# Power_SarSol.net
KiCad netlist of a schematic drawn in Altium Designer
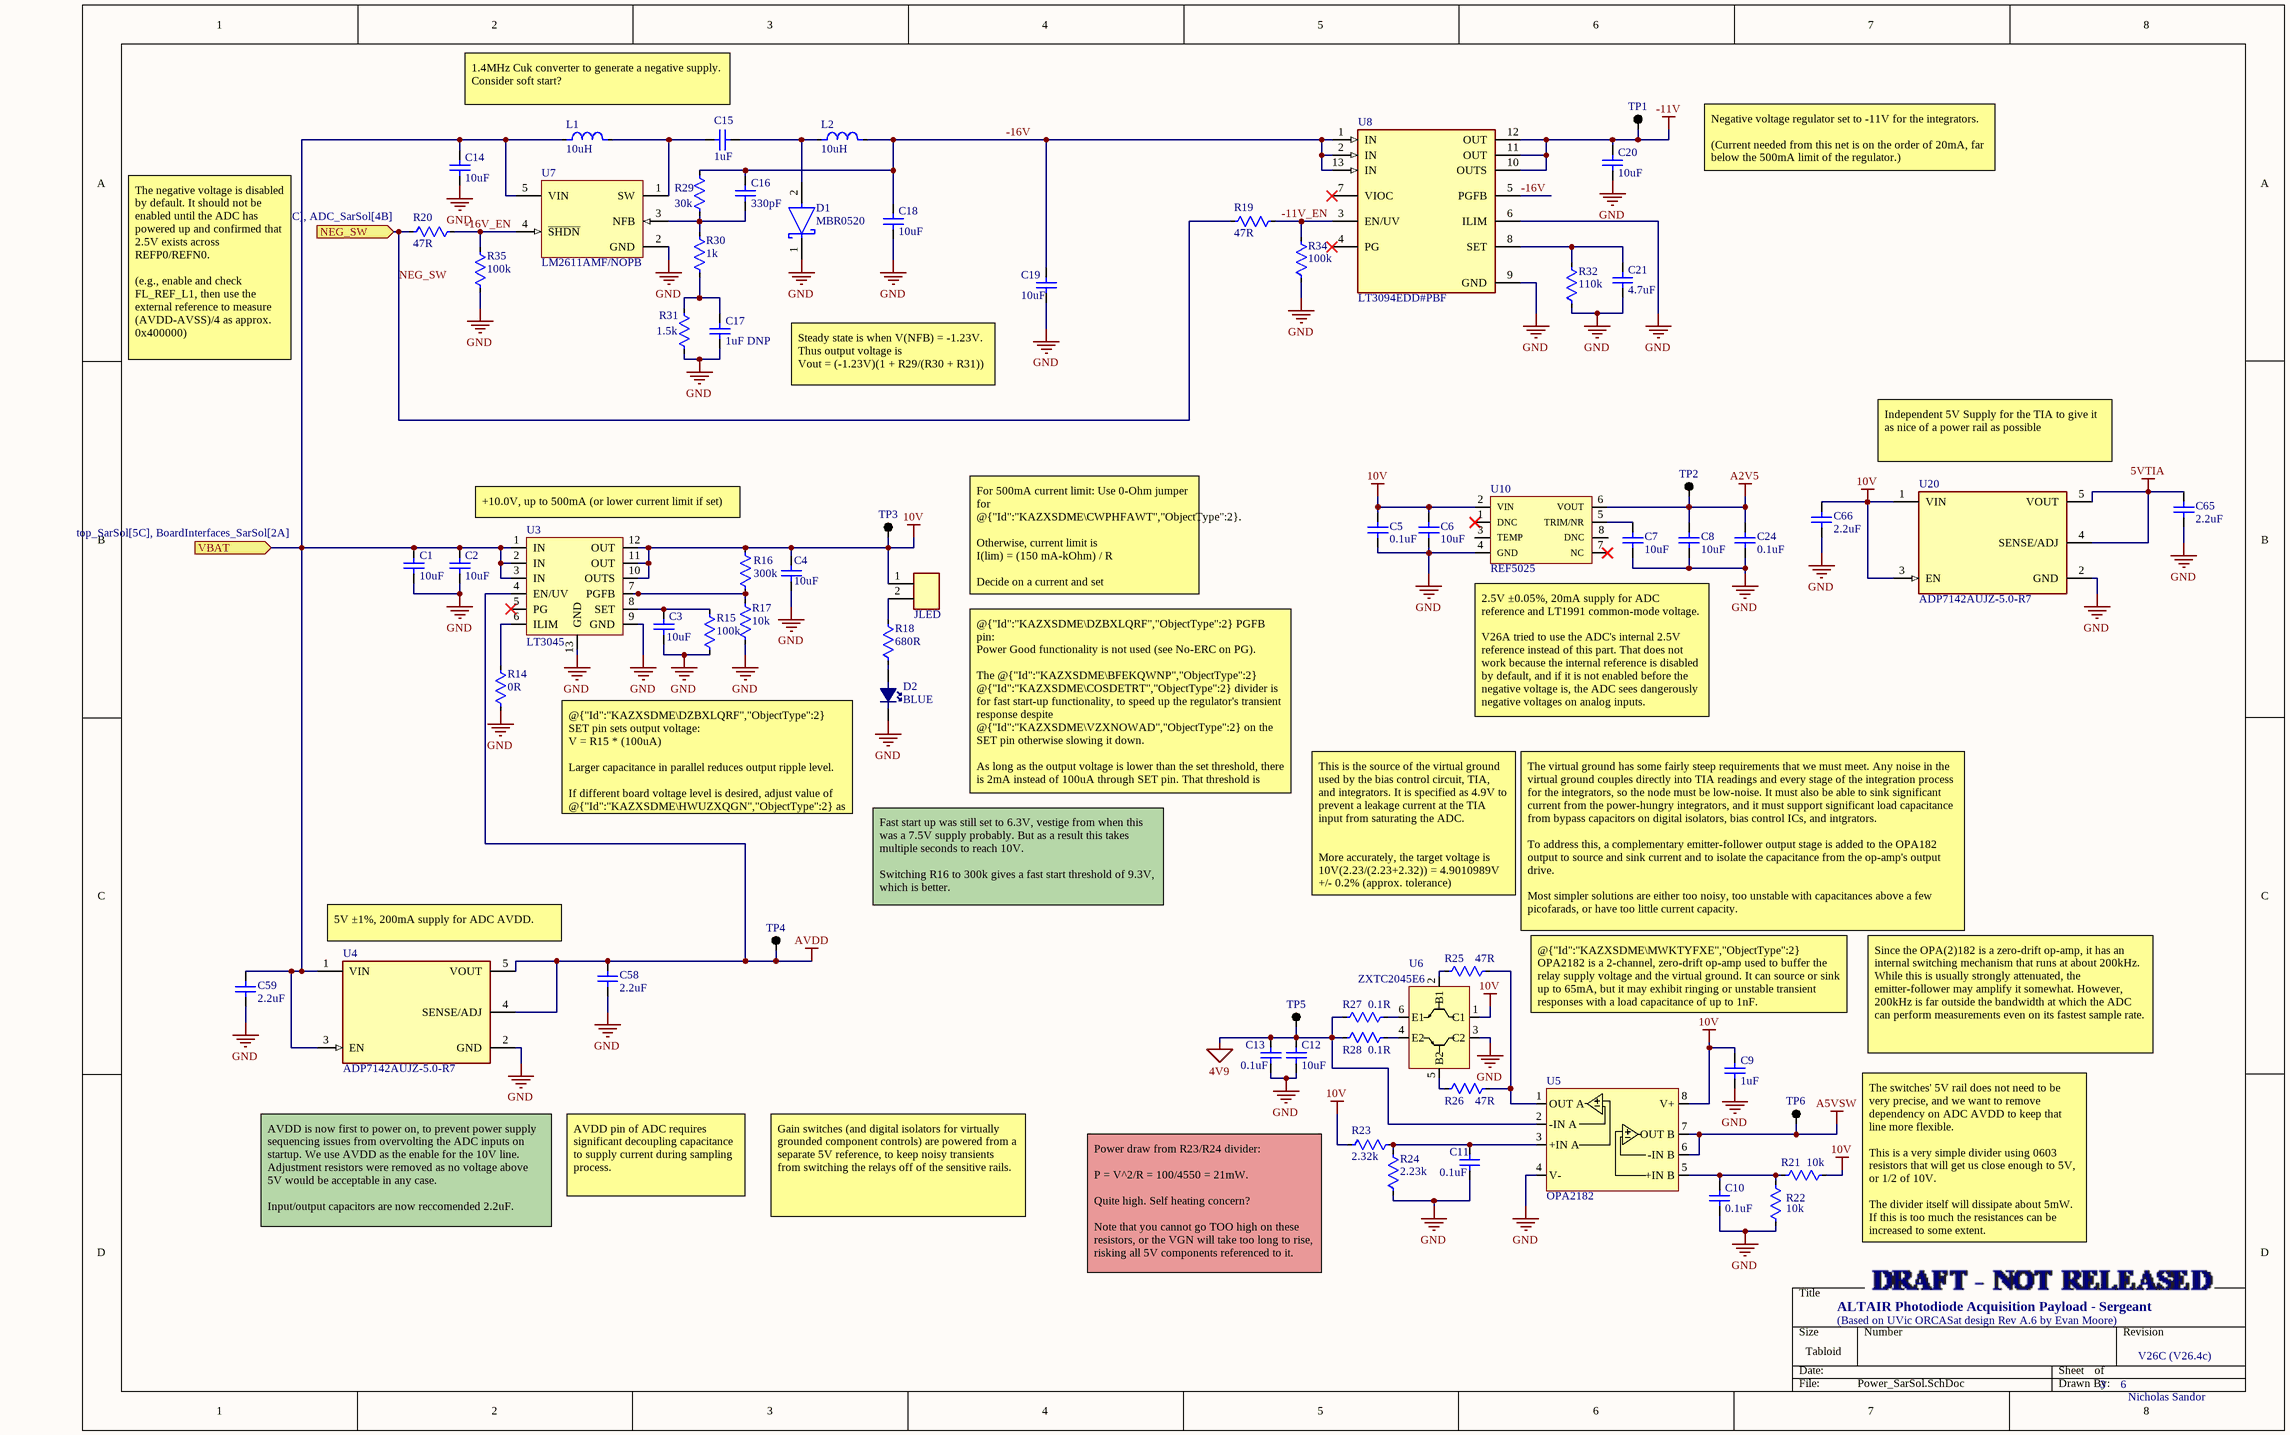
[diagram p0: Power_SarSol.SchDoc]

(export (version "E")
  (design (tool "Eeschema 10.0.6"))
  (components
    (comp (ref "C1")
      (value "10uF")
      (footprint "CAP 1206 IPC LOW DENSITY")
      (description "Murata GRT319R6YA106KE01D - Cap Ceramic 10uF 35V X5R 10% Pad SMD 1206 85C Automotive T/R")
      (fields (field (name "MF") "Murata") (field (name "MP") "GRT319R6YA106KE01D"))
      (libsource (lib "ALTAIR_PD_Capacitors") (part "CAP"))
    )
    (comp (ref "C2")
      (value "10uF")
      (footprint "CAP 1206 IPC LOW DENSITY")
      (description "Murata GRT319R6YA106KE01D - Cap Ceramic 10uF 35V X5R 10% Pad SMD 1206 85C Automotive T/R")
      (fields (field (name "MF") "Murata") (field (name "MP") "GRT319R6YA106KE01D"))
      (libsource (lib "ALTAIR_PD_Capacitors") (part "CAP"))
    )
    (comp (ref "C3")
      (value "10uF")
      (footprint "CAP 1206 IPC LOW DENSITY")
      (description "Murata GRT319R6YA106KE01D - Cap Ceramic 10uF 35V X5R 10% Pad SMD 1206 85C Automotive T/R")
      (fields (field (name "MF") "Murata") (field (name "MP") "GRT319R6YA106KE01D"))
      (libsource (lib "ALTAIR_PD_Capacitors") (part "CAP"))
    )
    (comp (ref "C4")
      (value "10uF")
      (footprint "CAP 1206 IPC LOW DENSITY")
      (description "Murata GRT319R6YA106KE01D - Cap Ceramic 10uF 35V X5R 10% Pad SMD 1206 85C Automotive T/R")
      (fields (field (name "MF") "Murata") (field (name "MP") "GRT319R6YA106KE01D"))
      (libsource (lib "ALTAIR_PD_Capacitors") (part "CAP"))
    )
    (comp (ref "C5")
      (value "0.1uF")
      (footprint "CAP 0603 IPC MID DENSITY")
      (description "Kemet C0603C104K5RACAUTO - Cap Ceramic 0.1uF 50V X7R 10% 0603 125C Paper T/R")
      (fields (field (name "MF") "Kemet") (field (name "MP") "C0603C104K5RACAUTO"))
      (libsource (lib "ALTAIR_PD_Capacitors") (part "CAP"))
    )
    (comp (ref "C6")
      (value "10uF")
      (footprint "CAP 0805 IPC MID DENSITY")
      (description "Murata GRM21BR61E106KA73L - Cap Ceramic 10uF 10% 25V X5R 0805")
      (fields (field (name "MF") "Murata") (field (name "MP") "GRM21BR61E106KA73L"))
      (libsource (lib "ALTAIR_PD_Capacitors") (part "CAP"))
    )
    (comp (ref "C7")
      (value "10uF")
      (footprint "CAP 0805 IPC MID DENSITY")
      (description "Murata GRM21BR61E106KA73L - Cap Ceramic 10uF 10% 25V X5R 0805")
      (fields (field (name "MF") "Murata") (field (name "MP") "GRM21BR61E106KA73L"))
      (libsource (lib "ALTAIR_PD_Capacitors") (part "CAP"))
    )
    (comp (ref "C8")
      (value "10uF")
      (footprint "CAP 0805 IPC MID DENSITY")
      (description "Murata GRM21BR61E106KA73L - Cap Ceramic 10uF 10% 25V X5R 0805")
      (fields (field (name "MF") "Murata") (field (name "MP") "GRM21BR61E106KA73L"))
      (libsource (lib "ALTAIR_PD_Capacitors") (part "CAP"))
    )
    (comp (ref "C9")
      (value "1uF")
      (footprint "CAP 0603 IPC MID DENSITY")
      (description "Murata GRT188R61H105KE13D - Cap MLCC AEC-Q200 X5R 1uF 50V 0603")
      (fields (field (name "MF") "Murata") (field (name "MP") "GRT188R61H105KE13D"))
      (libsource (lib "ALTAIR_PD_Capacitors") (part "CAP"))
    )
    (comp (ref "C10")
      (value "0.1uF")
      (footprint "CAP 0603 IPC MID DENSITY")
      (description "Kemet C0603C104K5RACAUTO - Cap Ceramic 0.1uF 50V X7R 10% 0603 125C Paper T/R")
      (fields (field (name "MF") "Kemet") (field (name "MP") "C0603C104K5RACAUTO"))
      (libsource (lib "ALTAIR_PD_Capacitors") (part "CAP"))
    )
    (comp (ref "C11")
      (value "0.1uF")
      (footprint "CAP 0603 IPC MID DENSITY")
      (description "Kemet C0603C104K5RACAUTO - Cap Ceramic 0.1uF 50V X7R 10% 0603 125C Paper T/R")
      (fields (field (name "MF") "Kemet") (field (name "MP") "C0603C104K5RACAUTO"))
      (libsource (lib "ALTAIR_PD_Capacitors") (part "CAP"))
    )
    (comp (ref "C12")
      (value "10uF")
      (footprint "CAP 1206 IPC LOW DENSITY")
      (description "Murata GRT319R6YA106KE01D - Cap Ceramic 10uF 35V X5R 10% Pad SMD 1206 85C Automotive T/R")
      (fields (field (name "MF") "Murata") (field (name "MP") "GRT319R6YA106KE01D"))
      (libsource (lib "ALTAIR_PD_Capacitors") (part "CAP"))
    )
    (comp (ref "C13")
      (value "0.1uF")
      (footprint "CAP 0603 IPC MID DENSITY")
      (description "Kemet C0603C104K5RACAUTO - Cap Ceramic 0.1uF 50V X7R 10% 0603 125C Paper T/R")
      (fields (field (name "MF") "Kemet") (field (name "MP") "C0603C104K5RACAUTO"))
      (libsource (lib "ALTAIR_PD_Capacitors") (part "CAP"))
    )
    (comp (ref "C14")
      (value "10uF")
      (footprint "CAP 0805 IPC MID DENSITY")
      (description "Murata GRM21BR61E106KA73L - Cap Ceramic 10uF 10% 25V X5R 0805")
      (fields (field (name "MF") "Murata") (field (name "MP") "GRM21BR61E106KA73L"))
      (libsource (lib "ALTAIR_PD_Capacitors") (part "CAP"))
    )
    (comp (ref "C15")
      (value "1uF")
      (footprint "CAP 0603 IPC MID DENSITY")
      (description "Murata GRT188R61H105KE13D - Cap MLCC AEC-Q200 X5R 1uF 50V 0603")
      (fields (field (name "MF") "Murata") (field (name "MP") "GRT188R61H105KE13D"))
      (libsource (lib "ALTAIR_PD_Capacitors") (part "CAP"))
    )
    (comp (ref "C16")
      (value "330pF")
      (footprint "CAP 1206 NON-IPC KEMET NP0")
      (description "Kemet C1206C331J5GACTU - Cap Ceramic 330pF 50V 5% NP0 1206")
      (fields (field (name "MF") "Kemet") (field (name "MP") "C1206C331J5GACTU"))
      (libsource (lib "ALTAIR_PD_Capacitors") (part "CAP"))
    )
    (comp (ref "C17")
      (value "1uF DNP")
      (footprint "CAP 0603 IPC MID DENSITY")
      (description "Murata GRT188R61H105KE13D - Cap MLCC AEC-Q200 X5R 1uF 50V 0603")
      (fields (field (name "MF") "Murata") (field (name "MP") "GRT188R61H105KE13D"))
      (libsource (lib "ALTAIR_PD_Capacitors") (part "CAP"))
    )
    (comp (ref "C18")
      (value "10uF")
      (footprint "CAP 0805 IPC MID DENSITY")
      (description "Murata GRM21BR61E106KA73L - Cap Ceramic 10uF 10% 25V X5R 0805")
      (fields (field (name "MF") "Murata") (field (name "MP") "GRM21BR61E106KA73L"))
      (libsource (lib "ALTAIR_PD_Capacitors") (part "CAP"))
    )
    (comp (ref "C19")
      (value "10uF")
      (footprint "CAP 0805 IPC MID DENSITY")
      (description "Murata GRM21BR61E106KA73L - Cap Ceramic 10uF 10% 25V X5R 0805")
      (fields (field (name "MF") "Murata") (field (name "MP") "GRM21BR61E106KA73L"))
      (libsource (lib "ALTAIR_PD_Capacitors") (part "CAP"))
    )
    (comp (ref "C20")
      (value "10uF")
      (footprint "CAP 0805 IPC MID DENSITY")
      (description "Murata GRM21BR61E106KA73L - Cap Ceramic 10uF 10% 25V X5R 0805")
      (fields (field (name "MF") "Murata") (field (name "MP") "GRM21BR61E106KA73L"))
      (libsource (lib "ALTAIR_PD_Capacitors") (part "CAP"))
    )
    (comp (ref "C21")
      (value "4.7uF")
      (footprint "CAP 0805 NON-IPC KEMET X5R")
      (description "Kemet C0805C475K8PACTU - Cap Ceramic 4.7uF 10V X5R 0805")
      (fields (field (name "MF") "Kemet") (field (name "MP") "C0805C475K8PACTU"))
      (libsource (lib "ALTAIR_PD_Capacitors") (part "CAP"))
    )
    (comp (ref "C24")
      (value "0.1uF")
      (footprint "CAP 0603 IPC MID DENSITY")
      (description "Kemet C0603C104K5RACAUTO - Cap Ceramic 0.1uF 50V X7R 10% 0603 125C Paper T/R")
      (fields (field (name "MF") "Kemet") (field (name "MP") "C0603C104K5RACAUTO"))
      (libsource (lib "ALTAIR_PD_Capacitors") (part "CAP"))
    )
    (comp (ref "C58")
      (value "2.2uF")
      (footprint "CAP 1206 UNKNOWN")
      (description "Cap, Nonpolar, Any, Must choose footprint manually")
      (libsource (lib "ALTAIR_PD_Capacitors") (part "CAP"))
    )
    (comp (ref "C59")
      (value "2.2uF")
      (footprint "CAP 1206 UNKNOWN")
      (description "Cap, Nonpolar, Any, Must choose footprint manually")
      (libsource (lib "ALTAIR_PD_Capacitors") (part "CAP"))
    )
    (comp (ref "C65")
      (value "2.2uF")
      (footprint "CAP 1206 UNKNOWN")
      (description "Cap, Nonpolar, Any, Must choose footprint manually")
      (libsource (lib "ALTAIR_PD_Capacitors") (part "CAP"))
    )
    (comp (ref "C66")
      (value "2.2uF")
      (footprint "CAP 1206 UNKNOWN")
      (description "Cap, Nonpolar, Any, Must choose footprint manually")
      (libsource (lib "ALTAIR_PD_Capacitors") (part "CAP"))
    )
    (comp (ref "D1")
      (value "MBR0520")
      (footprint "SOD-123 ONSEMI SMALL PADS")
      (description "DIODE SCHOTTKY 20V 500MA SOD123")
      (fields (field (name "MF") "onsemi") (field (name "MP") "MBR0520LT1G"))
      (libsource (lib "ALTAIR_PD_Diodes") (part "Schottky"))
    )
    (comp (ref "D2")
      (value "BLUE")
      (footprint "LED 0603 MID DENSITY")
      (description "LED BLUE CLEAR 0603 SMD")
      (fields (field (name "MF") "Wurth Electronics") (field (name "MP") "150060BS75000"))
      (libsource (lib "ALTAIR_PD_Diodes") (part "LED-blue"))
    )
    (comp (ref "JLED")
      (value "JLED")
      (footprint "ALTAIR_PD_Headers:JUMPER 2POS 1MM PITCH THT")
      (description "2x1 Header THT 1mm Pitch")
      (fields
        (field (name "MF") "GCT (GLOBAL CONNECTOR TECHNOLOGY)")
        (field (name "MP") "BC020-02-A-0200-0300-L-G")
      )
      (libsource (lib "ALTAIR_PD_Headers") (part "BC020-02-A-0200-0300-L-G"))
    )
    (comp (ref "L1")
      (value "10uH")
      (footprint "IND VLS3012CX-1 NONSTANDARD TDK")
      (description "TDK VLS3012CX-100M-1 - Inductor 10uH 20% 1.25A 0.324Ohm NonstandardPkg")
      (fields (field (name "TOLERANCE") "20%") (field (name "MF") "TDK Corporation"))
      (libsource (lib "ALTAIR_PD_Inductors") (part "IND"))
    )
    (comp (ref "L2")
      (value "10uH")
      (footprint "IND VLS3012CX-1 NONSTANDARD TDK")
      (description "TDK VLS3012CX-100M-1 - Inductor 10uH 20% 1.25A 0.324Ohm NonstandardPkg")
      (fields (field (name "TOLERANCE") "20%") (field (name "MF") "TDK Corporation"))
      (libsource (lib "ALTAIR_PD_Inductors") (part "IND"))
    )
    (comp (ref "R14")
      (value "0R")
      (footprint "RES 0603 IPC MID DENSITY")
      (description "Vishay CRCW06030000Z0EA - Res 0 Ohms 1/8W SMD 0603")
      (fields (field (name "MF") "Vishay Dale") (field (name "MP") "CRCW06030000Z0EA"))
      (libsource (lib "ALTAIR_PD_Resistors") (part "RES"))
    )
    (comp (ref "R15")
      (value "100k")
      (footprint "RES 0603 IPC MID DENSITY")
      (description "Panasonic ERA-3ARB104V - Res SMD 0603 0.1% 0.10W T.C. 10ppm 100K")
      (fields (field (name "MF") "Panasonic Electronic Components") (field (name "MP") "ERA-3ARB104V"))
      (libsource (lib "ALTAIR_PD_Resistors") (part "RES"))
    )
    (comp (ref "R16")
      (value "300k")
      (footprint "RES 0603 IPC MID DENSITY")
      (description "Vishay MCT06030C2003FP500 - Res SMD 200kOhm 1% 1/10W 0603")
      (fields (field (name "MF") "Vishay Dale") (field (name "MP") "MCT06030C2003FP500"))
      (libsource (lib "ALTAIR_PD_Resistors") (part "RES"))
    )
    (comp (ref "R17")
      (value "10k")
      (footprint "RES 0603 IPC MID DENSITY")
      (description "Vishay CRCW060310K0FKEA SMD 0603 10k, CRCW e3 Series, 75V, thick film, 100mW")
      (fields (field (name "MF") "Vishay Dale") (field (name "MP") "CRCW060310K0FKEA"))
      (libsource (lib "ALTAIR_PD_Resistors") (part "RES"))
    )
    (comp (ref "R18")
      (value "680R")
      (footprint "RES 0603 IPC MID DENSITY")
      (description "Panasonic ERJ-3EKF6800V - Res SMD 680 Ohm 1% 1/10W 0603")
      (fields (field (name "MF") "Panasonic Electronic Components") (field (name "MP") "ERJ-3EKF6800V"))
      (libsource (lib "ALTAIR_PD_Resistors") (part "RES"))
    )
    (comp (ref "R19")
      (value "47R")
      (footprint "RES 0603 IPC MID DENSITY")
      (description "Vishay CRCW060347R0JNEA - Res 47Ohm 5% 1/8W SMD 0603")
      (fields (field (name "MF") "Vishay Dale") (field (name "MP") "CRCW060347R0JNEA"))
      (libsource (lib "ALTAIR_PD_Resistors") (part "RES"))
    )
    (comp (ref "R20")
      (value "47R")
      (footprint "RES 0603 IPC MID DENSITY")
      (description "Vishay CRCW060347R0JNEA - Res 47Ohm 5% 1/8W SMD 0603")
      (fields (field (name "MF") "Vishay Dale") (field (name "MP") "CRCW060347R0JNEA"))
      (libsource (lib "ALTAIR_PD_Resistors") (part "RES"))
    )
    (comp (ref "R21")
      (value "10k")
      (footprint "RES 0603 IPC MID DENSITY")
      (description "Vishay CRCW060310K0FKEA SMD 0603 10k, CRCW e3 Series, 75V, thick film, 100mW")
      (fields (field (name "MF") "Vishay Dale") (field (name "MP") "CRCW060310K0FKEA"))
      (libsource (lib "ALTAIR_PD_Resistors") (part "RES"))
    )
    (comp (ref "R22")
      (value "10k")
      (footprint "RES 0603 IPC MID DENSITY")
      (description "Vishay CRCW060310K0FKEA SMD 0603 10k, CRCW e3 Series, 75V, thick film, 100mW")
      (fields (field (name "MF") "Vishay Dale") (field (name "MP") "CRCW060310K0FKEA"))
      (libsource (lib "ALTAIR_PD_Resistors") (part "RES"))
    )
    (comp (ref "R23")
      (value "2.32k")
      (footprint "RES 0603 IPC MID DENSITY")
      (description "Vishay TNPW06032K32BEEA - Res 2.32k 0.1% 0.21W SMD 0603")
      (fields (field (name "MF") "Vishay Dale") (field (name "MP") "TNPW06032K32BEEA"))
      (libsource (lib "ALTAIR_PD_Resistors") (part "RES"))
    )
    (comp (ref "R24")
      (value "2.23k")
      (footprint "RES 0603 IPC MID DENSITY")
      (description "KOA Speer RN73R1JTTD2231B25 - Res 2.23k 0.1% 1/10W SMD 0603")
      (fields (field (name "MF") "KOA Speer Electronics, Inc.") (field (name "MP") "RN73R1JTTD2231B25"))
      (libsource (lib "ALTAIR_PD_Resistors") (part "RES"))
    )
    (comp (ref "R25")
      (value "47R")
      (footprint "RES 0402 NON-IPC SEI")
      (description "Stackpole RMCF0402JT47R0 - Res 47Ohm 5% 0.063W 0402 Thick Film AEC-Q200 compliant")
      (fields (field (name "MF") "Stackpole Electronics Inc.") (field (name "MP") "RMCF0402JT47R0"))
      (libsource (lib "ALTAIR_PD_Resistors") (part "RES"))
    )
    (comp (ref "R26")
      (value "47R")
      (footprint "RES 0402 NON-IPC SEI")
      (description "Stackpole RMCF0402JT47R0 - Res 47Ohm 5% 0.063W 0402 Thick Film AEC-Q200 compliant")
      (fields (field (name "MF") "Stackpole Electronics Inc.") (field (name "MP") "RMCF0402JT47R0"))
      (libsource (lib "ALTAIR_PD_Resistors") (part "RES"))
    )
    (comp (ref "R27")
      (value "0.1R")
      (footprint "RES 0402 NON-IPC YAGEO")
      (description "Yageo RL0402JR-070R1L - Res 0.1Ohm 5% 1/16W SMD 0402")
      (fields (field (name "MF") "YAGEO") (field (name "MP") "RL0402JR-070R1L"))
      (libsource (lib "ALTAIR_PD_Resistors") (part "RES"))
    )
    (comp (ref "R28")
      (value "0.1R")
      (footprint "RES 0402 NON-IPC YAGEO")
      (description "Yageo RL0402JR-070R1L - Res 0.1Ohm 5% 1/16W SMD 0402")
      (fields (field (name "MF") "YAGEO") (field (name "MP") "RL0402JR-070R1L"))
      (libsource (lib "ALTAIR_PD_Resistors") (part "RES"))
    )
    (comp (ref "R29")
      (value "30k")
      (footprint "RES 0805 IPC HIGH DENSITY")
      (description "Panasonic ERA-6AEB303V - Res 30kOhm 0.1% 1/8W 0805")
      (fields (field (name "MF") "Panasonic Electronic Components") (field (name "MP") "ERA-6AEB303V"))
      (libsource (lib "ALTAIR_PD_Resistors") (part "RES"))
    )
    (comp (ref "R30")
      (value "1k")
      (footprint "RES 0402 IPC LOW DENSITY YAGEO")
      (description "Yageo RC0402FR-071KL - Res 1kOhm 1% 1/16W 0402")
      (fields (field (name "MF") "YAGEO") (field (name "MP") "RC0402FR-071KL"))
      (libsource (lib "ALTAIR_PD_Resistors") (part "RES"))
    )
    (comp (ref "R31")
      (value "1.5k")
      (footprint "RES 1206 NON-IPC VISHAY")
      (description "Vishay TNPU12061K50BZEN00 - Res 1.5kOhm 0.1% 1/4W 1206")
      (fields (field (name "MF") "Vishay Dale") (field (name "MP") "TNPU12061K50BZEN00"))
      (libsource (lib "ALTAIR_PD_Resistors") (part "RES"))
    )
    (comp (ref "R32")
      (value "110k")
      (footprint "RES 0603 IPC MID DENSITY")
      (description "Panasonic ERA-3AEB114V - Res 110k 0.1% 1/10W SMD 0603")
      (fields (field (name "MF") "Panasonic Electronic Components") (field (name "MP") "ERA-3AEB114V"))
      (libsource (lib "ALTAIR_PD_Resistors") (part "RES"))
    )
    (comp (ref "R34")
      (value "100k")
      (footprint "RES 0603 IPC MID DENSITY")
      (description "Panasonic ERJ-3GEYJ104V - Res 100k 5% 1/10W SMD 0603")
      (fields (field (name "MF") "Panasonic Electronic Components") (field (name "MP") "ERJ-3GEYJ104V"))
      (libsource (lib "ALTAIR_PD_Resistors") (part "RES"))
    )
    (comp (ref "R35")
      (value "100k")
      (footprint "RES 0603 IPC MID DENSITY")
      (description "Panasonic ERJ-3GEYJ104V - Res 100k 5% 1/10W SMD 0603")
      (fields (field (name "MF") "Panasonic Electronic Components") (field (name "MP") "ERJ-3GEYJ104V"))
      (libsource (lib "ALTAIR_PD_Resistors") (part "RES"))
    )
    (comp (ref "TP1")
      (value "Testpoint")
      (footprint "TESTPOINT THT")
      (libsource (lib "ALTAIR_PD_Testpoint") (part "Testpoint"))
    )
    (comp (ref "TP2")
      (value "Testpoint")
      (footprint "TESTPOINT THT")
      (libsource (lib "ALTAIR_PD_Testpoint") (part "Testpoint"))
    )
    (comp (ref "TP3")
      (value "Testpoint")
      (footprint "TESTPOINT THT")
      (libsource (lib "ALTAIR_PD_Testpoint") (part "Testpoint"))
    )
    (comp (ref "TP4")
      (value "Testpoint")
      (footprint "TESTPOINT THT")
      (libsource (lib "ALTAIR_PD_Testpoint") (part "Testpoint"))
    )
    (comp (ref "TP5")
      (value "Testpoint")
      (footprint "TESTPOINT THT")
      (libsource (lib "ALTAIR_PD_Testpoint") (part "Testpoint"))
    )
    (comp (ref "TP6")
      (value "Testpoint")
      (footprint "TESTPOINT THT")
      (libsource (lib "ALTAIR_PD_Testpoint") (part "Testpoint"))
    )
    (comp (ref "U3")
      (value "LT3045")
      (footprint "12-TSOP 0.65MM PITCH 3MM WIDTH EP IPC MID DENSITY")
      (description "20V 500mA Ultralow Noise Ultrahigh PSRR Adjustable Linear Regulator 260V Dropout MSOP-12")
      (fields (field (name "MF") "Analog Devices / Linear Technology") (field (name "MP") "LT3045EMSE#PBF"))
      (libsource (lib "ALTAIR_PD_Regulators") (part "LT3045"))
    )
    (comp (ref "U4")
      (value "ADP7142AUJZ-5.0-R7")
      (footprint "SOT23-5 HIGH DENSITY AD")
      (description "1.2-40V 200mA Low Noise CMOS LDO Adjustable Linear Regulator TSOT23")
      (fields
        (field (name "OCTOPART") "https://octopart.com/adp7142aujz-r7-analog+devices-38928114")
        (field (name "MF") "Analog Devices")
      )
      (libsource (lib "ALTAIR_PD_Regulators") (part "ADP7142AUJZ-R7"))
    )
    (comp (ref "U5")
      (value "OPA2182")
      (footprint "8-TSSOP 0.65MM PITCH 4.4MM WIDTH IPC MID DENSITY")
      (fields (field (name "MF") "Texas Instruments") (field (name "MP") "OPA2182IDGKR"))
      (libsource (lib "ALTAIR_PD_Amplifiers") (part "OPA2182IDBV"))
    )
    (comp (ref "U6")
      (value "ZXTC2045E6")
      (footprint "SOT23-6 NON-IPC DIODES")
      (description "BJT Array, 1NPN 1PNP, VCE(sat) 375mV, hFE 300, Breakdown 30V, 6-SOT-23")
      (fields (field (name "MF") "Diodes Incorporated") (field (name "MP") "ZXTC2045E6TA"))
      (libsource (lib "ALTAIR_PD_BJTs") (part "ZXTC2045E6"))
    )
    (comp (ref "U7")
      (value "LM2611AMF/NOPB")
      (footprint "SOT23-5 MID DENSITY")
      (description "1.4MHz Cuk Converter, 5-pin SOT-23, Pb-Free")
      (fields (field (name "MF") "Texas Instruments"))
      (libsource (lib "ALTAIR_PD_Converters") (part "LM2611AMF"))
    )
    (comp (ref "U8")
      (value "LT3094EDD#PBF")
      (footprint "12DFN 3x3MM EP IPC MID DENSITY")
      (description "-20V 500mA Ultralow Noise Ultrahigh PSRR Adjustable Negative Linear Regulator 12DFN")
      (fields (field (name "MF") "Analog Devices"))
      (libsource (lib "ALTAIR_PD_Regulators") (part "LT3094EDD#PBF"))
    )
    (comp (ref "U10")
      (value "REF5025")
      (footprint "8-TSOP 0.65MM PITCH 3MM WIDTH IPC MID DENSITY")
      (description "2.5V±0.05% Voltage Reference 8VSSOP")
      (fields (field (name "MF") "Texas Instruments") (field (name "MP") "REF5025IDGKR"))
      (libsource (lib "ALTAIR_PD_MiscPower") (part "REF5050IDGKR"))
    )
    (comp (ref "U20")
      (value "ADP7142AUJZ-5.0-R7")
      (footprint "SOT23-5 HIGH DENSITY AD")
      (description "1.2-40V 200mA Low Noise CMOS LDO Adjustable Linear Regulator TSOT23")
      (fields
        (field (name "OCTOPART") "https://octopart.com/adp7142aujz-r7-analog+devices-38928114")
        (field (name "MF") "Analog Devices")
      )
      (libsource (lib "ALTAIR_PD_Regulators") (part "ADP7142AUJZ-R7"))
    )
  )
  (nets
    (net (code "1") (name "-11V") (class "Default")
      (node (ref "C20") (pin "1") (pinfunction "1_1") (pintype "passive"))
      (node (ref "TP1") (pin "1") (pinfunction "1_1") (pintype "passive"))
      (node (ref "U8") (pin "10") (pinfunction "OUTS_10") (pintype "power_in"))
      (node (ref "U8") (pin "11") (pinfunction "OUT_11") (pintype "power_in"))
      (node (ref "U8") (pin "12") (pinfunction "OUT_12") (pintype "power_in"))
    )
    (net (code "2") (name "/-11V_EN") (class "Default")
      (node (ref "R19") (pin "1") (pinfunction "1_1") (pintype "passive"))
      (node (ref "R34") (pin "1") (pinfunction "1_1") (pintype "passive"))
      (node (ref "U8") (pin "3") (pinfunction "EN/UV_3") (pintype "passive"))
    )
    (net (code "3") (name "/-16V") (class "Default")
      (node (ref "C16") (pin "1") (pinfunction "1_1") (pintype "passive"))
      (node (ref "C18") (pin "1") (pinfunction "1_1") (pintype "passive"))
      (node (ref "C19") (pin "1") (pinfunction "1_1") (pintype "passive"))
      (node (ref "L2") (pin "2") (pinfunction "2_2") (pintype "passive"))
      (node (ref "R29") (pin "2") (pinfunction "2_2") (pintype "passive"))
      (node (ref "U8") (pin "1") (pinfunction "IN_1") (pintype "input"))
      (node (ref "U8") (pin "13") (pinfunction "IN_13") (pintype "input"))
      (node (ref "U8") (pin "2") (pinfunction "IN_2") (pintype "input"))
      (node (ref "U8") (pin "5") (pinfunction "PGFB_5") (pintype "passive"))
    )
    (net (code "4") (name "/-16V_EN") (class "Default")
      (node (ref "R20") (pin "1") (pinfunction "1_1") (pintype "passive"))
      (node (ref "R35") (pin "1") (pinfunction "1_1") (pintype "passive"))
      (node (ref "U7") (pin "4") (pinfunction "~{SHDN}_4") (pintype "input"))
    )
    (net (code "5") (name "/NEG_SW") (class "Default")
      (node (ref "R19") (pin "2") (pinfunction "2_2") (pintype "passive"))
      (node (ref "R20") (pin "2") (pinfunction "2_2") (pintype "passive"))
    )
    (net (code "6") (name "/VBAT") (class "Default")
      (node (ref "C1") (pin "2") (pinfunction "2_2") (pintype "passive"))
      (node (ref "C14") (pin "2") (pinfunction "2_2") (pintype "passive"))
      (node (ref "C2") (pin "2") (pinfunction "2_2") (pintype "passive"))
      (node (ref "C59") (pin "1") (pinfunction "1_1") (pintype "passive"))
      (node (ref "L1") (pin "1") (pinfunction "1_1") (pintype "passive"))
      (node (ref "U3") (pin "1") (pinfunction "IN_1") (pintype "passive"))
      (node (ref "U3") (pin "2") (pinfunction "IN_2") (pintype "passive"))
      (node (ref "U3") (pin "3") (pinfunction "IN_3") (pintype "passive"))
      (node (ref "U4") (pin "1") (pinfunction "VIN_1") (pintype "power_in"))
      (node (ref "U4") (pin "3") (pinfunction "EN_3") (pintype "input"))
      (node (ref "U7") (pin "5") (pinfunction "VIN_5") (pintype "power_in"))
    )
    (net (code "7") (name "4V9") (class "Default")
      (node (ref "C12") (pin "2") (pinfunction "2_2") (pintype "passive"))
      (node (ref "C13") (pin "2") (pinfunction "2_2") (pintype "passive"))
      (node (ref "R27") (pin "1") (pinfunction "1_1") (pintype "passive"))
      (node (ref "R28") (pin "1") (pinfunction "1_1") (pintype "passive"))
      (node (ref "TP5") (pin "1") (pinfunction "1_1") (pintype "passive"))
      (node (ref "U5") (pin "2") (pinfunction "-IN_A_2") (pintype "passive"))
    )
    (net (code "8") (name "5VTIA") (class "Default")
      (node (ref "C65") (pin "1") (pinfunction "1_1") (pintype "passive"))
      (node (ref "U20") (pin "4") (pinfunction "SENSE/ADJ_4") (pintype "passive"))
      (node (ref "U20") (pin "5") (pinfunction "VOUT_5") (pintype "passive"))
    )
    (net (code "9") (name "10V") (class "Default")
      (node (ref "C4") (pin "2") (pinfunction "2_2") (pintype "passive"))
      (node (ref "C5") (pin "1") (pinfunction "1_1") (pintype "passive"))
      (node (ref "C6") (pin "2") (pinfunction "2_2") (pintype "passive"))
      (node (ref "C66") (pin "1") (pinfunction "1_1") (pintype "passive"))
      (node (ref "C9") (pin "2") (pinfunction "2_2") (pintype "passive"))
      (node (ref "JLED") (pin "1") (pinfunction "1_1") (pintype "passive"))
      (node (ref "R16") (pin "2") (pinfunction "2_2") (pintype "passive"))
      (node (ref "R21") (pin "2") (pinfunction "2_2") (pintype "passive"))
      (node (ref "R23") (pin "2") (pinfunction "2_2") (pintype "passive"))
      (node (ref "TP3") (pin "1") (pinfunction "1_1") (pintype "passive"))
      (node (ref "U10") (pin "2") (pinfunction "VIN_2") (pintype "passive"))
      (node (ref "U20") (pin "1") (pinfunction "VIN_1") (pintype "power_in"))
      (node (ref "U20") (pin "3") (pinfunction "EN_3") (pintype "input"))
      (node (ref "U3") (pin "10") (pinfunction "OUTS_10") (pintype "passive"))
      (node (ref "U3") (pin "11") (pinfunction "OUT_11") (pintype "passive"))
      (node (ref "U3") (pin "12") (pinfunction "OUT_12") (pintype "passive"))
      (node (ref "U5") (pin "8") (pinfunction "V+_8") (pintype "passive"))
      (node (ref "U6") (pin "1") (pinfunction "C1_1") (pintype "passive"))
    )
    (net (code "10") (name "A2V5") (class "Default")
      (node (ref "C24") (pin "1") (pinfunction "1_1") (pintype "passive"))
      (node (ref "C8") (pin "2") (pinfunction "2_2") (pintype "passive"))
      (node (ref "TP2") (pin "1") (pinfunction "1_1") (pintype "passive"))
      (node (ref "U10") (pin "6") (pinfunction "VOUT_6") (pintype "passive"))
    )
    (net (code "11") (name "A5VSW") (class "Default")
      (node (ref "TP6") (pin "1") (pinfunction "1_1") (pintype "passive"))
      (node (ref "U5") (pin "6") (pinfunction "-IN_B_6") (pintype "passive"))
      (node (ref "U5") (pin "7") (pinfunction "OUT_B_7") (pintype "passive"))
    )
    (net (code "12") (name "AVDD") (class "Default")
      (node (ref "C58") (pin "1") (pinfunction "1_1") (pintype "passive"))
      (node (ref "TP4") (pin "1") (pinfunction "1_1") (pintype "passive"))
      (node (ref "U3") (pin "4") (pinfunction "EN/UV_4") (pintype "passive"))
      (node (ref "U4") (pin "4") (pinfunction "SENSE/ADJ_4") (pintype "passive"))
      (node (ref "U4") (pin "5") (pinfunction "VOUT_5") (pintype "passive"))
    )
    (net (code "13") (name "GND") (class "Default")
      (node (ref "C1") (pin "1") (pinfunction "1_1") (pintype "passive"))
      (node (ref "C10") (pin "1") (pinfunction "1_1") (pintype "passive"))
      (node (ref "C11") (pin "1") (pinfunction "1_1") (pintype "passive"))
      (node (ref "C12") (pin "1") (pinfunction "1_1") (pintype "passive"))
      (node (ref "C13") (pin "1") (pinfunction "1_1") (pintype "passive"))
      (node (ref "C14") (pin "1") (pinfunction "1_1") (pintype "passive"))
      (node (ref "C17") (pin "2") (pinfunction "2_2") (pintype "passive"))
      (node (ref "C18") (pin "2") (pinfunction "2_2") (pintype "passive"))
      (node (ref "C19") (pin "2") (pinfunction "2_2") (pintype "passive"))
      (node (ref "C2") (pin "1") (pinfunction "1_1") (pintype "passive"))
      (node (ref "C20") (pin "2") (pinfunction "2_2") (pintype "passive"))
      (node (ref "C21") (pin "2") (pinfunction "2_2") (pintype "passive"))
      (node (ref "C24") (pin "2") (pinfunction "2_2") (pintype "passive"))
      (node (ref "C3") (pin "1") (pinfunction "1_1") (pintype "passive"))
      (node (ref "C4") (pin "1") (pinfunction "1_1") (pintype "passive"))
      (node (ref "C5") (pin "2") (pinfunction "2_2") (pintype "passive"))
      (node (ref "C58") (pin "2") (pinfunction "2_2") (pintype "passive"))
      (node (ref "C59") (pin "2") (pinfunction "2_2") (pintype "passive"))
      (node (ref "C6") (pin "1") (pinfunction "1_1") (pintype "passive"))
      (node (ref "C65") (pin "2") (pinfunction "2_2") (pintype "passive"))
      (node (ref "C66") (pin "2") (pinfunction "2_2") (pintype "passive"))
      (node (ref "C7") (pin "2") (pinfunction "2_2") (pintype "passive"))
      (node (ref "C8") (pin "1") (pinfunction "1_1") (pintype "passive"))
      (node (ref "C9") (pin "1") (pinfunction "1_1") (pintype "passive"))
      (node (ref "D1") (pin "1") (pinfunction "C_1") (pintype "passive"))
      (node (ref "D2") (pin "1") (pinfunction "1_1") (pintype "passive"))
      (node (ref "R14") (pin "1") (pinfunction "1_1") (pintype "passive"))
      (node (ref "R15") (pin "1") (pinfunction "1_1") (pintype "passive"))
      (node (ref "R17") (pin "1") (pinfunction "1_1") (pintype "passive"))
      (node (ref "R22") (pin "1") (pinfunction "1_1") (pintype "passive"))
      (node (ref "R24") (pin "1") (pinfunction "1_1") (pintype "passive"))
      (node (ref "R31") (pin "1") (pinfunction "1_1") (pintype "passive"))
      (node (ref "R32") (pin "2") (pinfunction "2_2") (pintype "passive"))
      (node (ref "R34") (pin "2") (pinfunction "2_2") (pintype "passive"))
      (node (ref "R35") (pin "2") (pinfunction "2_2") (pintype "passive"))
      (node (ref "U10") (pin "4") (pinfunction "GND_4") (pintype "passive"))
      (node (ref "U20") (pin "2") (pinfunction "GND_2") (pintype "power_in"))
      (node (ref "U3") (pin "13") (pinfunction "GND_13") (pintype "passive"))
      (node (ref "U3") (pin "9") (pinfunction "GND_9") (pintype "passive"))
      (node (ref "U4") (pin "2") (pinfunction "GND_2") (pintype "power_in"))
      (node (ref "U5") (pin "4") (pinfunction "V-_4") (pintype "passive"))
      (node (ref "U6") (pin "3") (pinfunction "C2_3") (pintype "passive"))
      (node (ref "U7") (pin "2") (pinfunction "GND_2") (pintype "power_in"))
      (node (ref "U8") (pin "6") (pinfunction "ILIM_6") (pintype "passive"))
      (node (ref "U8") (pin "9") (pinfunction "GND_9") (pintype "power_in"))
    )
    (net (code "14") (name "Net-(C17-Pad1)") (class "Default")
      (node (ref "C17") (pin "1") (pinfunction "1_1") (pintype "passive"))
      (node (ref "R30") (pin "1") (pinfunction "1_1") (pintype "passive"))
      (node (ref "R31") (pin "2") (pinfunction "2_2") (pintype "passive"))
    )
    (net (code "15") (name "Net-(D1-A)") (class "Default")
      (node (ref "C15") (pin "2") (pinfunction "2_2") (pintype "passive"))
      (node (ref "D1") (pin "2") (pinfunction "A_2") (pintype "passive"))
      (node (ref "L2") (pin "1") (pinfunction "1_1") (pintype "passive"))
    )
    (net (code "16") (name "Net-(D2-Pad2)") (class "Default")
      (node (ref "D2") (pin "2") (pinfunction "2_2") (pintype "passive"))
      (node (ref "R18") (pin "1") (pinfunction "1_1") (pintype "passive"))
    )
    (net (code "17") (name "Net-(JLED-Pad2)") (class "Default")
      (node (ref "JLED") (pin "2") (pinfunction "2_2") (pintype "passive"))
      (node (ref "R18") (pin "2") (pinfunction "2_2") (pintype "passive"))
    )
    (net (code "18") (name "Net-(U3-ILIM)") (class "Default")
      (node (ref "R14") (pin "2") (pinfunction "2_2") (pintype "passive"))
      (node (ref "U3") (pin "6") (pinfunction "ILIM_6") (pintype "passive"))
    )
    (net (code "19") (name "Net-(U3-PGFB)") (class "Default")
      (node (ref "R16") (pin "1") (pinfunction "1_1") (pintype "passive"))
      (node (ref "R17") (pin "2") (pinfunction "2_2") (pintype "passive"))
      (node (ref "U3") (pin "7") (pinfunction "PGFB_7") (pintype "passive"))
    )
    (net (code "20") (name "Net-(U3-SET)") (class "Default")
      (node (ref "C3") (pin "2") (pinfunction "2_2") (pintype "passive"))
      (node (ref "R15") (pin "2") (pinfunction "2_2") (pintype "passive"))
      (node (ref "U3") (pin "8") (pinfunction "SET_8") (pintype "passive"))
    )
    (net (code "21") (name "Net-(U5-+IN_A)") (class "Default")
      (node (ref "C11") (pin "2") (pinfunction "2_2") (pintype "passive"))
      (node (ref "R23") (pin "1") (pinfunction "1_1") (pintype "passive"))
      (node (ref "R24") (pin "2") (pinfunction "2_2") (pintype "passive"))
      (node (ref "U5") (pin "3") (pinfunction "+IN_A_3") (pintype "passive"))
    )
    (net (code "22") (name "Net-(U5-+IN_B)") (class "Default")
      (node (ref "C10") (pin "2") (pinfunction "2_2") (pintype "passive"))
      (node (ref "R21") (pin "1") (pinfunction "1_1") (pintype "passive"))
      (node (ref "R22") (pin "2") (pinfunction "2_2") (pintype "passive"))
      (node (ref "U5") (pin "5") (pinfunction "+IN_B_5") (pintype "passive"))
    )
    (net (code "23") (name "Net-(U5-OUT_A)") (class "Default")
      (node (ref "R25") (pin "2") (pinfunction "2_2") (pintype "passive"))
      (node (ref "R26") (pin "2") (pinfunction "2_2") (pintype "passive"))
      (node (ref "U5") (pin "1") (pinfunction "OUT_A_1") (pintype "passive"))
    )
    (net (code "24") (name "Net-(U6-B1)") (class "Default")
      (node (ref "R25") (pin "1") (pinfunction "1_1") (pintype "passive"))
      (node (ref "U6") (pin "2") (pinfunction "B1_2") (pintype "passive"))
    )
    (net (code "25") (name "Net-(U6-B2)") (class "Default")
      (node (ref "R26") (pin "1") (pinfunction "1_1") (pintype "passive"))
      (node (ref "U6") (pin "5") (pinfunction "B2_5") (pintype "passive"))
    )
    (net (code "26") (name "Net-(U6-E1)") (class "Default")
      (node (ref "R27") (pin "2") (pinfunction "2_2") (pintype "passive"))
      (node (ref "U6") (pin "6") (pinfunction "E1_6") (pintype "passive"))
    )
    (net (code "27") (name "Net-(U6-E2)") (class "Default")
      (node (ref "R28") (pin "2") (pinfunction "2_2") (pintype "passive"))
      (node (ref "U6") (pin "4") (pinfunction "E2_4") (pintype "passive"))
    )
    (net (code "28") (name "Net-(U7-NFB)") (class "Default")
      (node (ref "C16") (pin "2") (pinfunction "2_2") (pintype "passive"))
      (node (ref "R29") (pin "1") (pinfunction "1_1") (pintype "passive"))
      (node (ref "R30") (pin "2") (pinfunction "2_2") (pintype "passive"))
      (node (ref "U7") (pin "3") (pinfunction "NFB_3") (pintype "input"))
    )
    (net (code "29") (name "Net-(U7-SW)") (class "Default")
      (node (ref "C15") (pin "1") (pinfunction "1_1") (pintype "passive"))
      (node (ref "L1") (pin "2") (pinfunction "2_2") (pintype "passive"))
      (node (ref "U7") (pin "1") (pinfunction "SW_1") (pintype "power_in"))
    )
    (net (code "30") (name "Net-(U8-SET)") (class "Default")
      (node (ref "C21") (pin "1") (pinfunction "1_1") (pintype "passive"))
      (node (ref "R32") (pin "1") (pinfunction "1_1") (pintype "passive"))
      (node (ref "U8") (pin "8") (pinfunction "SET_8") (pintype "passive"))
    )
    (net (code "31") (name "Net-(U10-TRIM{slash}NR)") (class "Default")
      (node (ref "C7") (pin "1") (pinfunction "1_1") (pintype "passive"))
      (node (ref "U10") (pin "5") (pinfunction "TRIM/NR_5") (pintype "passive"))
    )
    (net (code "32") (name "unconnected-(U3-PG-Pad5)") (class "Default")
      (node (ref "U3") (pin "5") (pinfunction "PG_5") (pintype "passive+no_connect"))
    )
    (net (code "33") (name "unconnected-(U8-PG-Pad4)") (class "Default")
      (node (ref "U8") (pin "4") (pinfunction "PG_4") (pintype "passive+no_connect"))
    )
    (net (code "34") (name "unconnected-(U8-VIOC-Pad7)") (class "Default")
      (node (ref "U8") (pin "7") (pinfunction "VIOC_7") (pintype "passive+no_connect"))
    )
    (net (code "35") (name "unconnected-(U10-DNC-Pad1)") (class "Default")
      (node (ref "U10") (pin "1") (pinfunction "DNC_1") (pintype "passive+no_connect"))
    )
    (net (code "36") (name "unconnected-(U10-DNC-Pad8)") (class "Default")
      (node (ref "U10") (pin "8") (pinfunction "DNC_8") (pintype "passive"))
    )
    (net (code "37") (name "unconnected-(U10-NC-Pad7)") (class "Default")
      (node (ref "U10") (pin "7") (pinfunction "NC_7") (pintype "passive+no_connect"))
    )
    (net (code "38") (name "unconnected-(U10-TEMP-Pad3)") (class "Default")
      (node (ref "U10") (pin "3") (pinfunction "TEMP_3") (pintype "passive"))
    )
  )
)
